# Sheet2.net
KiCad netlist of a schematic drawn in Altium Designer
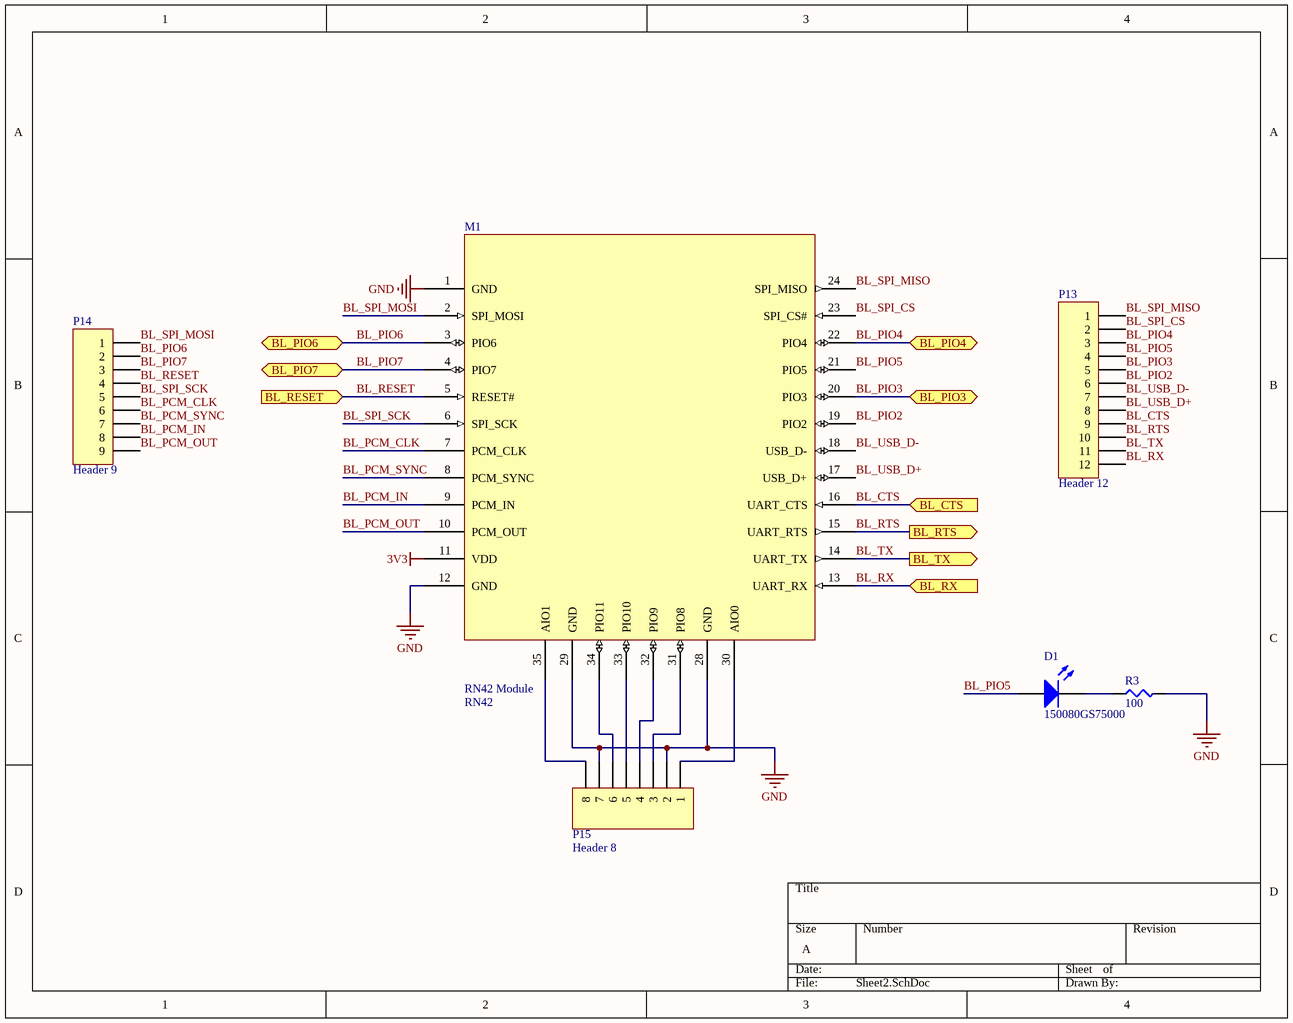
[diagram p0: Sheet2.SchDoc]

(export (version "E")
  (design (tool "Eeschema 10.0.6"))
  (components
    (comp (ref "D1")
      (value "150080GS75000")
      (footprint "0805_A")
      (description "SMD mono-color Chip LED, WL-SMCW, Green")
      (libsource (lib "WL-SMCW SMD chip LED top view mono-color waterclear") (part "150080GS75000"))
    )
    (comp (ref "M1")
      (value "RN42 Module")
      (footprint "RN42-LAND")
      (fields (field (name "ALTIUM_VALUE") "RN42"))
      (libsource (lib "Dwl-Altium-Schematic-Symbol-Library") (part "RN42MOD"))
    )
    (comp (ref "P13")
      (value "Header 12")
      (footprint "HDR1X12")
      (description "Header, 12-Pin")
      (fields (field (name "PUBLISHER") "Altium Limited"))
      (libsource (lib "Miscellaneous Connectors") (part "Header 12"))
    )
    (comp (ref "P14")
      (value "Header 9")
      (footprint "HDR1X9")
      (description "Header, 9-Pin")
      (fields (field (name "PUBLISHER") "Altium Limited"))
      (libsource (lib "Miscellaneous Connectors") (part "Header 9"))
    )
    (comp (ref "P15")
      (value "Header 8")
      (footprint "HDR1X8")
      (description "Header, 8-Pin")
      (fields (field (name "PUBLISHER") "Altium Limited"))
      (libsource (lib "Miscellaneous Connectors") (part "Header 8"))
    )
    (comp (ref "R3")
      (value "100")
      (footprint "SMD-0805-RES")
      (description "RES SMD 100 OHM 1% 1/8W 0805")
      (fields (field (name "PART NUMBER") "ERJ-6ENF1000V") (field (name "DIGI-KEY PART NUMBER") "P100CCT-ND"))
      (libsource (lib "Panasonic_ERJ_0805") (part "ERJ-6ENF1000V"))
    )
  )
  (nets
    (net (code "1") (name "/BL_CTS") (class "Default")
      (node (ref "M1") (pin "16") (pinfunction "UART_CTS_16") (pintype "input"))
      (node (ref "P13") (pin "9") (pinfunction "9_9") (pintype "passive"))
    )
    (net (code "2") (name "/BL_PCM_CLK") (class "Default")
      (node (ref "M1") (pin "7") (pinfunction "PCM_CLK_7") (pintype "passive"))
      (node (ref "P14") (pin "6") (pinfunction "6_6") (pintype "passive"))
    )
    (net (code "3") (name "/BL_PCM_IN") (class "Default")
      (node (ref "M1") (pin "9") (pinfunction "PCM_IN_9") (pintype "passive"))
      (node (ref "P14") (pin "8") (pinfunction "8_8") (pintype "passive"))
    )
    (net (code "4") (name "/BL_PCM_OUT") (class "Default")
      (node (ref "M1") (pin "10") (pinfunction "PCM_OUT_10") (pintype "passive"))
      (node (ref "P14") (pin "9") (pinfunction "9_9") (pintype "passive"))
    )
    (net (code "5") (name "/BL_PCM_SYNC") (class "Default")
      (node (ref "M1") (pin "8") (pinfunction "PCM_SYNC_8") (pintype "passive"))
      (node (ref "P14") (pin "7") (pinfunction "7_7") (pintype "passive"))
    )
    (net (code "6") (name "/BL_PIO2") (class "Default")
      (node (ref "M1") (pin "19") (pinfunction "PIO2_19") (pintype "bidirectional"))
      (node (ref "P13") (pin "6") (pinfunction "6_6") (pintype "passive"))
    )
    (net (code "7") (name "/BL_PIO3") (class "Default")
      (node (ref "M1") (pin "20") (pinfunction "PIO3_20") (pintype "bidirectional"))
      (node (ref "P13") (pin "5") (pinfunction "5_5") (pintype "passive"))
    )
    (net (code "8") (name "/BL_PIO4") (class "Default")
      (node (ref "M1") (pin "22") (pinfunction "PIO4_22") (pintype "bidirectional"))
      (node (ref "P13") (pin "3") (pinfunction "3_3") (pintype "passive"))
    )
    (net (code "9") (name "/BL_PIO5") (class "Default")
      (node (ref "D1") (pin "2") (pinfunction "A_2") (pintype "passive"))
      (node (ref "M1") (pin "21") (pinfunction "PIO5_21") (pintype "bidirectional"))
      (node (ref "P13") (pin "4") (pinfunction "4_4") (pintype "passive"))
    )
    (net (code "10") (name "/BL_PIO6") (class "Default")
      (node (ref "M1") (pin "3") (pinfunction "PIO6_3") (pintype "bidirectional"))
      (node (ref "P14") (pin "2") (pinfunction "2_2") (pintype "passive"))
    )
    (net (code "11") (name "/BL_PIO7") (class "Default")
      (node (ref "M1") (pin "4") (pinfunction "PIO7_4") (pintype "bidirectional"))
      (node (ref "P14") (pin "3") (pinfunction "3_3") (pintype "passive"))
    )
    (net (code "12") (name "/BL_RESET") (class "Default")
      (node (ref "M1") (pin "5") (pinfunction "RESET#_5") (pintype "input"))
      (node (ref "P14") (pin "4") (pinfunction "4_4") (pintype "passive"))
    )
    (net (code "13") (name "/BL_RTS") (class "Default")
      (node (ref "M1") (pin "15") (pinfunction "UART_RTS_15") (pintype "output"))
      (node (ref "P13") (pin "10") (pinfunction "10_10") (pintype "passive"))
    )
    (net (code "14") (name "/BL_RX") (class "Default")
      (node (ref "M1") (pin "13") (pinfunction "UART_RX_13") (pintype "input"))
      (node (ref "P13") (pin "12") (pinfunction "12_12") (pintype "passive"))
    )
    (net (code "15") (name "/BL_SPI_CS") (class "Default")
      (node (ref "M1") (pin "23") (pinfunction "SPI_CS#_23") (pintype "input"))
      (node (ref "P13") (pin "2") (pinfunction "2_2") (pintype "passive"))
    )
    (net (code "16") (name "/BL_SPI_MISO") (class "Default")
      (node (ref "M1") (pin "24") (pinfunction "SPI_MISO_24") (pintype "output"))
      (node (ref "P13") (pin "1") (pinfunction "1_1") (pintype "passive"))
    )
    (net (code "17") (name "/BL_SPI_MOSI") (class "Default")
      (node (ref "M1") (pin "2") (pinfunction "SPI_MOSI_2") (pintype "input"))
      (node (ref "P14") (pin "1") (pinfunction "1_1") (pintype "passive"))
    )
    (net (code "18") (name "/BL_SPI_SCK") (class "Default")
      (node (ref "M1") (pin "6") (pinfunction "SPI_SCK_6") (pintype "input"))
      (node (ref "P14") (pin "5") (pinfunction "5_5") (pintype "passive"))
    )
    (net (code "19") (name "/BL_TX") (class "Default")
      (node (ref "M1") (pin "14") (pinfunction "UART_TX_14") (pintype "output"))
      (node (ref "P13") (pin "11") (pinfunction "11_11") (pintype "passive"))
    )
    (net (code "20") (name "/BL_USB_D+") (class "Default")
      (node (ref "M1") (pin "17") (pinfunction "USB_D+_17") (pintype "bidirectional"))
      (node (ref "P13") (pin "8") (pinfunction "8_8") (pintype "passive"))
    )
    (net (code "21") (name "/BL_USB_D-") (class "Default")
      (node (ref "M1") (pin "18") (pinfunction "USB_D-_18") (pintype "bidirectional"))
      (node (ref "P13") (pin "7") (pinfunction "7_7") (pintype "passive"))
    )
    (net (code "22") (name "3V3") (class "Default")
      (node (ref "M1") (pin "11") (pinfunction "VDD_11") (pintype "power_in"))
    )
    (net (code "23") (name "GND") (class "Default")
      (node (ref "M1") (pin "1") (pinfunction "GND_1") (pintype "power_in"))
      (node (ref "M1") (pin "12") (pinfunction "GND_12") (pintype "power_in"))
      (node (ref "M1") (pin "28") (pinfunction "GND_28") (pintype "power_in"))
      (node (ref "M1") (pin "29") (pinfunction "GND_29") (pintype "power_in"))
      (node (ref "P15") (pin "2") (pinfunction "2_2") (pintype "passive"))
      (node (ref "P15") (pin "7") (pinfunction "7_7") (pintype "passive"))
      (node (ref "R3") (pin "2") (pinfunction "2_2") (pintype "passive"))
    )
    (net (code "24") (name "Net-(D1-K)") (class "Default")
      (node (ref "D1") (pin "1") (pinfunction "K_1") (pintype "passive"))
      (node (ref "R3") (pin "1") (pinfunction "1_1") (pintype "passive"))
    )
    (net (code "25") (name "Net-(M1-AIO0)") (class "Default")
      (node (ref "M1") (pin "30") (pinfunction "AIO0_30") (pintype "passive"))
      (node (ref "P15") (pin "1") (pinfunction "1_1") (pintype "passive"))
    )
    (net (code "26") (name "Net-(M1-AIO1)") (class "Default")
      (node (ref "M1") (pin "35") (pinfunction "AIO1_35") (pintype "passive"))
      (node (ref "P15") (pin "8") (pinfunction "8_8") (pintype "passive"))
    )
    (net (code "27") (name "Net-(M1-PIO8)") (class "Default")
      (node (ref "M1") (pin "31") (pinfunction "PIO8_31") (pintype "bidirectional"))
      (node (ref "P15") (pin "3") (pinfunction "3_3") (pintype "passive"))
    )
    (net (code "28") (name "Net-(M1-PIO9)") (class "Default")
      (node (ref "M1") (pin "32") (pinfunction "PIO9_32") (pintype "bidirectional"))
      (node (ref "P15") (pin "4") (pinfunction "4_4") (pintype "passive"))
    )
    (net (code "29") (name "Net-(M1-PIO10)") (class "Default")
      (node (ref "M1") (pin "33") (pinfunction "PIO10_33") (pintype "bidirectional"))
      (node (ref "P15") (pin "5") (pinfunction "5_5") (pintype "passive"))
    )
    (net (code "30") (name "Net-(M1-PIO11)") (class "Default")
      (node (ref "M1") (pin "34") (pinfunction "PIO11_34") (pintype "bidirectional"))
      (node (ref "P15") (pin "6") (pinfunction "6_6") (pintype "passive"))
    )
  )
)
